# Sheet1.net
KiCad netlist of a schematic drawn in Altium Designer
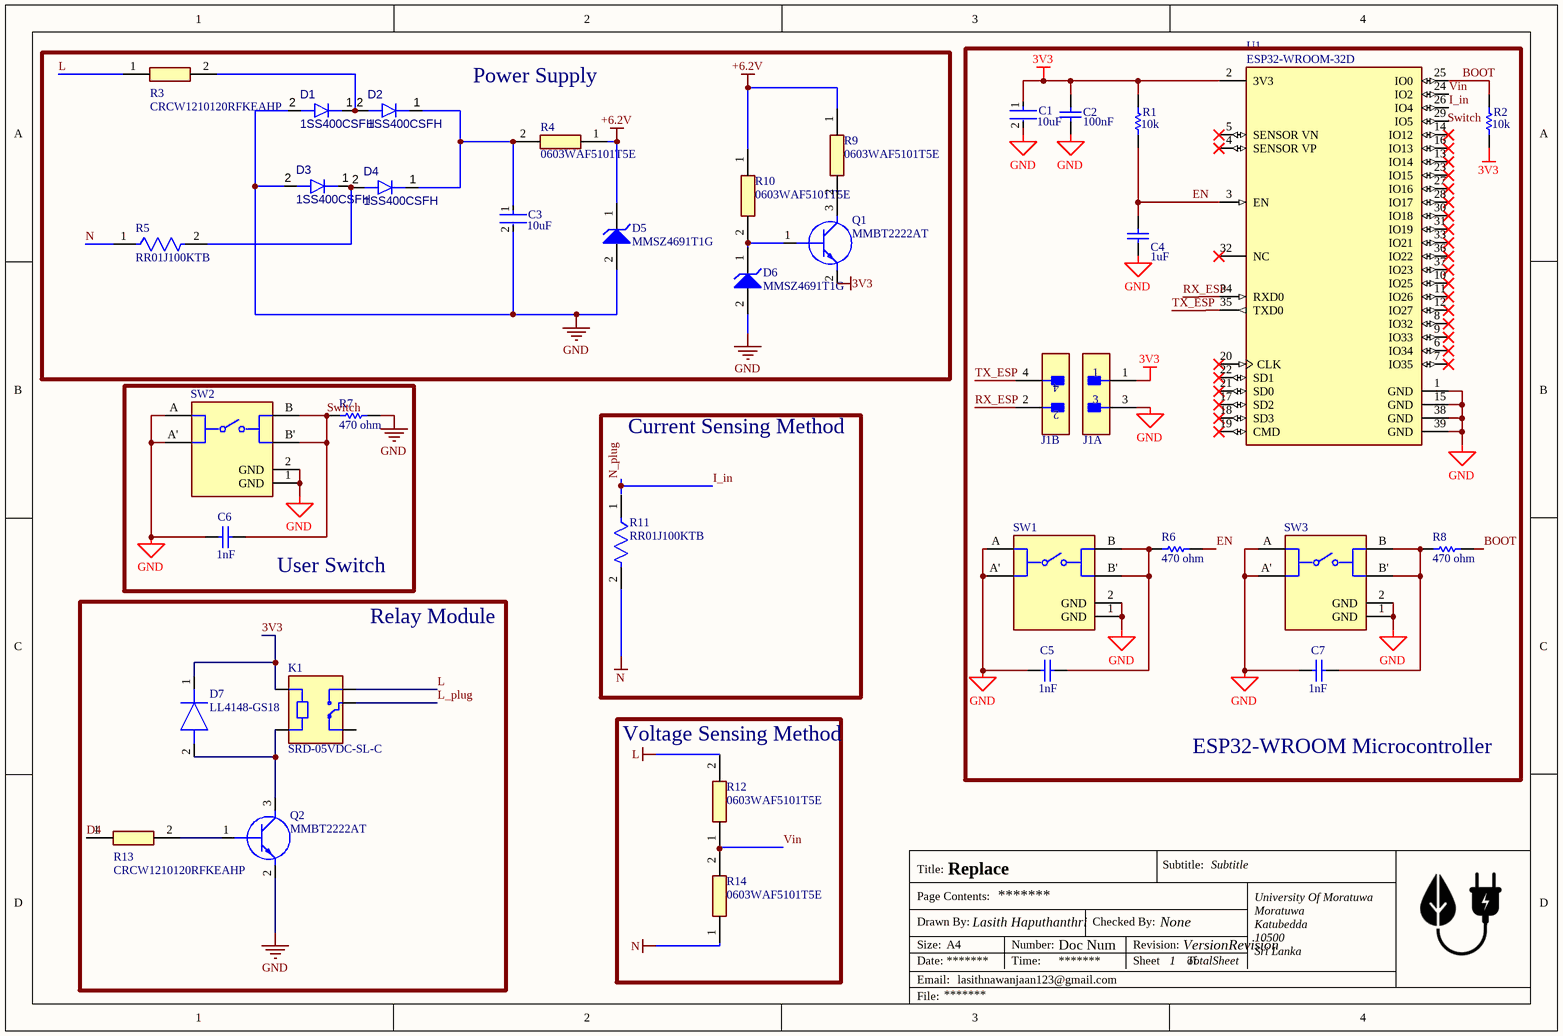
[diagram p0: Sheet1.SchDoc]

(export (version "E")
  (design (tool "Eeschema 10.0.6"))
  (components
    (comp (ref "C1")
      (value "1206YD106KAT2A")
      (footprint "FP-1206-L_3_2_0_2-W_1_6_0-IPC_B")
      (description "General Purpose Ceramic Capacitor, 1206, 10uF, 10%, X5R, 15%, 16V")
      (fields
        (field (name "TOLERANCE") "10%")
        (field (name "CAPACITANCE") "10uF")
        (field (name "VOLTAGE") "16V")
      )
      (libsource (lib "Altium Content Vault") (part "02cd4be3c70576c341d710602a673aa"))
    )
    (comp (ref "C2")
      (value "100nF")
      (footprint "CAPC2013X140X50LL20T25")
      (fields
        (field (name "MANUFACTURER") "AVX Interconnect / Elco")
        (field (name "PART NUMBER") "08055F104KAT2A")
      )
      (libsource (lib "Altium Content Vault") (part "CAP"))
    )
    (comp (ref "C3")
      (value "1206YD106KAT2A")
      (footprint "FP-1206-L_3_2_0_2-W_1_6_0-IPC_B")
      (description "General Purpose Ceramic Capacitor, 1206, 10uF, 10%, X5R, 15%, 16V")
      (fields
        (field (name "TOLERANCE") "10%")
        (field (name "CAPACITANCE") "10uF")
        (field (name "VOLTAGE") "16V")
      )
      (libsource (lib "Altium Content Vault") (part "02cd4be3c70576c341d710602a673aa"))
    )
    (comp (ref "C4")
      (value "C0805C105K4PACTU")
      (footprint "CAPC2013X145X50LL20T25")
      (fields (field (name "MANUFACTURER") "Kemet") (field (name "PARAMETER 1") "1uF"))
      (libsource (lib "Altium Content Vault") (part "CAP"))
    )
    (comp (ref "C5")
      (value "VJ0805D102KXAAJ")
      (footprint "CAPC2013X145X48LL20T23")
      (fields (field (name "MANUFACTURER") "Vitramon") (field (name "PARAMETER 1") "1nF"))
      (libsource (lib "Altium Content Vault") (part "CAP"))
    )
    (comp (ref "C6")
      (value "VJ0805D102KXAAJ")
      (footprint "CAPC2013X145X48LL20T23")
      (fields (field (name "MANUFACTURER") "Vitramon") (field (name "PARAMETER 1") "1nF"))
      (libsource (lib "Altium Content Vault") (part "CAP"))
    )
    (comp (ref "C7")
      (value "VJ0805D102KXAAJ")
      (footprint "CAPC2013X145X48LL20T23")
      (fields (field (name "MANUFACTURER") "Vitramon") (field (name "PARAMETER 1") "1nF"))
      (libsource (lib "Altium Content Vault") (part "CAP"))
    )
    (comp (ref "D1")
      (value "1SS400CSFH")
      (footprint "ROHM-VMN2-2_V")
      (description "Switching Diode (High Speed Switching), 80 V, 100 mA, 2-Pin SOD-923, RoHS, Tape and Reel")
      (libsource (lib "University of Moratuwa") (part "D-KA-2"))
    )
    (comp (ref "D2")
      (value "1SS400CSFH")
      (footprint "ROHM-VMN2-2_V")
      (description "Switching Diode (High Speed Switching), 80 V, 100 mA, 2-Pin SOD-923, RoHS, Tape and Reel")
      (libsource (lib "University of Moratuwa") (part "D-KA-2"))
    )
    (comp (ref "D3")
      (value "1SS400CSFH")
      (footprint "ROHM-VMN2-2_V")
      (description "Switching Diode (High Speed Switching), 80 V, 100 mA, 2-Pin SOD-923, RoHS, Tape and Reel")
      (libsource (lib "University of Moratuwa") (part "D-KA-2"))
    )
    (comp (ref "D4")
      (value "1SS400CSFH")
      (footprint "ROHM-VMN2-2_V")
      (description "Switching Diode (High Speed Switching), 80 V, 100 mA, 2-Pin SOD-923, RoHS, Tape and Reel")
      (libsource (lib "University of Moratuwa") (part "D-KA-2"))
    )
    (comp (ref "D5")
      (value "MMSZ4691T1G")
      (footprint "ONSC-SOD-123-2-425-04_V")
      (description "Zener Voltage Regulator, 500 mW, 2-Pin SOD-123, Pb-Free, Tape and Reel")
      (fields (field (name "MANUFACTURER") "On Semiconductor"))
      (libsource (lib "Altium Content Vault") (part "ONSC-K1A2-2"))
    )
    (comp (ref "D6")
      (value "MMSZ4691T1G")
      (footprint "ONSC-SOD-123-2-425-04_V")
      (description "Zener Voltage Regulator, 500 mW, 2-Pin SOD-123, Pb-Free, Tape and Reel")
      (fields (field (name "MANUFACTURER") "On Semiconductor"))
      (libsource (lib "Altium Content Vault") (part "ONSC-K1A2-2"))
    )
    (comp (ref "D7")
      (value "LL4148-GS18")
      (footprint "SamacSys:SOD-80")
      (description "Diode")
      (fields (field (name "MOUSER PART NUMBER") "78-LL4148-GS18"))
      (libsource (lib "*") (part "LL4148-GS18"))
    )
    (comp (ref "J1")
      (value "PEC02DABN")
      (footprint "FP-PEC02DABN-MFG")
      (description "CONN HEADER VERT 4POS 2.54MM")
      (libsource (lib "Altium Content Vault") (part "1621473add15499e993d6bbd36d0f06"))
    )
    (comp (ref "K1")
      (value "SRD-05VDC-SL-C")
      (footprint "RELAY_SRD-05VDC-SL-C")
      (fields (field (name "MF") "Songle Relay"))
      (libsource (lib "SRD-05VDC-SL-C") (part "SRD-05VDC-SL-C"))
    )
    (comp (ref "Q1")
      (value "MMBT2222AT")
      (footprint "SamacSys:SOTFL50P160X78-3N")
      (description "Transistor BJT NPN")
      (fields (field (name "MOUSER PART NUMBER") "512-MMBT2222AT"))
      (libsource (lib "*") (part "MMBT2222AT"))
    )
    (comp (ref "Q2")
      (value "MMBT2222AT")
      (footprint "SamacSys:SOTFL50P160X78-3N")
      (description "Transistor BJT NPN")
      (fields (field (name "MOUSER PART NUMBER") "512-MMBT2222AT"))
      (libsource (lib "*") (part "MMBT2222AT"))
    )
    (comp (ref "R1")
      (value "RC0805FR-0710KL")
      (footprint "RESC2013X60X35NL10T20")
      (description "Chip Resistor, 10 KOhm, +/- 1%, 0.125 W, -55 to 155 degC, 0805 (2012 Metric), RoHS, Tape and Reel")
      (fields (field (name "MANUFACTURER") "Yageo") (field (name "PARAMETER 1") "10k"))
      (libsource (lib "Altium Content Vault") (part "RES-2"))
    )
    (comp (ref "R2")
      (value "RC0805FR-0710KL")
      (footprint "RESC2013X60X35NL10T20")
      (description "Chip Resistor, 10 KOhm, +/- 1%, 0.125 W, -55 to 155 degC, 0805 (2012 Metric), RoHS, Tape and Reel")
      (fields (field (name "MANUFACTURER") "Yageo") (field (name "PARAMETER 1") "10k"))
      (libsource (lib "Altium Content Vault") (part "RES-2"))
    )
    (comp (ref "R3")
      (value "CRCW1210120RFKEAHP")
      (footprint "SamacSys:RESC3225X70N")
      (description "Resistor")
      (fields (field (name "MOUSER PART NUMBER") "71-CRCW1210120RFKEAH"))
      (libsource (lib "*") (part "CRCW1210120RFKEAHP"))
    )
    (comp (ref "R4")
      (value "0603WAF5101T5E")
      (footprint "SamacSys:RESC1608X55N")
      (description "Resistor")
      (libsource (lib "") (part "0603WAF5101T5E_2"))
    )
    (comp (ref "R5")
      (value "RR01J100KTB")
      (footprint "FP-RR01-MFG")
      (description "RES 100K OHM 5% 1W AXIAL")
      (fields (field (name "TOLERANCE") "5%"))
      (libsource (lib "Altium Content Vault") (part "1029c3af85768c4190bb7ad29bc67b5"))
    )
    (comp (ref "R6")
      (value "CRCW0805470RFKEA")
      (footprint "RESC2013X50X30LL20T20")
      (fields (field (name "MANUFACTURER") "Vishay Dale") (field (name "PARAMETER 1") "470 ohm"))
      (libsource (lib "Altium Content Vault") (part "RES"))
    )
    (comp (ref "R7")
      (value "CRCW0805470RFKEA")
      (footprint "RESC2013X50X30LL20T20")
      (fields (field (name "MANUFACTURER") "Vishay Dale") (field (name "PARAMETER 1") "470 ohm"))
      (libsource (lib "Altium Content Vault") (part "RES"))
    )
    (comp (ref "R8")
      (value "CRCW0805470RFKEA")
      (footprint "RESC2013X50X30LL20T20")
      (fields (field (name "MANUFACTURER") "Vishay Dale") (field (name "PARAMETER 1") "470 ohm"))
      (libsource (lib "Altium Content Vault") (part "RES"))
    )
    (comp (ref "R9")
      (value "0603WAF5101T5E")
      (footprint "SamacSys:RESC1608X55N")
      (description "Resistor")
      (libsource (lib "") (part "0603WAF5101T5E_1"))
    )
    (comp (ref "R10")
      (value "0603WAF5101T5E")
      (footprint "SamacSys:RESC1608X55N")
      (description "Resistor")
      (libsource (lib "") (part "0603WAF5101T5E_1"))
    )
    (comp (ref "R11")
      (value "RR01J100KTB")
      (footprint "FP-RR01-MFG")
      (description "RES 100K OHM 5% 1W AXIAL")
      (fields (field (name "TOLERANCE") "5%"))
      (libsource (lib "Altium Content Vault") (part "1029c3af85768c4190bb7ad29bc67b5"))
    )
    (comp (ref "R12")
      (value "0603WAF5101T5E")
      (footprint "SamacSys:RESC1608X55N")
      (description "Resistor")
      (libsource (lib "*") (part "0603WAF5101T5E"))
    )
    (comp (ref "R13")
      (value "CRCW1210120RFKEAHP")
      (footprint "SamacSys:RESC3225X70N")
      (description "Resistor")
      (fields (field (name "MOUSER PART NUMBER") "71-CRCW1210120RFKEAH"))
      (libsource (lib "*") (part "CRCW1210120RFKEAHP"))
    )
    (comp (ref "R14")
      (value "0603WAF5101T5E")
      (footprint "SamacSys:RESC1608X55N")
      (description "Resistor")
      (libsource (lib "*") (part "0603WAF5101T5E"))
    )
    (comp (ref "SW1")
      (value "EVQ-PLMA15")
      (footprint "FP-EVQ-PLMA15-MFG")
      (description "SWITCH TACTILE SPST-NO 0.02A 15V")
      (fields
        (field (name "OCTOPART") "https://octopart.com/evq-plma15-panasonic-39850235")
        (field (name "MANUFACTURER") "Panasonic Electronic Components")
      )
      (libsource (lib "Altium Content Vault") (part "fc7b47d2e4813f0909612a6c4f63938"))
    )
    (comp (ref "SW2")
      (value "EVQ-PLMA15")
      (footprint "FP-EVQ-PLMA15-MFG")
      (description "SWITCH TACTILE SPST-NO 0.02A 15V")
      (fields
        (field (name "OCTOPART") "https://octopart.com/evq-plma15-panasonic-39850235")
        (field (name "MANUFACTURER") "Panasonic Electronic Components")
      )
      (libsource (lib "Altium Content Vault") (part "fc7b47d2e4813f0909612a6c4f63938"))
    )
    (comp (ref "SW3")
      (value "EVQ-PLMA15")
      (footprint "FP-EVQ-PLMA15-MFG")
      (description "SWITCH TACTILE SPST-NO 0.02A 15V")
      (fields
        (field (name "OCTOPART") "https://octopart.com/evq-plma15-panasonic-39850235")
        (field (name "MANUFACTURER") "Panasonic Electronic Components")
      )
      (libsource (lib "Altium Content Vault") (part "fc7b47d2e4813f0909612a6c4f63938"))
    )
    (comp (ref "U1")
      (value "ESP32-WROOM-32D")
      (footprint "FP-ESP32-WROOM-32D-MFG")
      (description "WIFI MODULE 32MBITS SPI FLASH")
      (fields
        (field (name "OCTOPART") "https://octopart.com/esp32-wroom-32d-espressif+systems-91040050")
        (field (name "MANUFACTURER") "Espressif Systems")
      )
      (libsource (lib "Altium Content Vault") (part "a031a76f8c27026a7a7f4657ff233a3"))
    )
  )
  (nets
    (net (code "1") (name "+6.2V") (class "Default")
      (node (ref "D5") (pin "1") (pinfunction "K_1") (pintype "passive"))
      (node (ref "R10") (pin "1") (pinfunction "1_1") (pintype "passive"))
      (node (ref "R4") (pin "1") (pinfunction "1_1") (pintype "passive"))
      (node (ref "R9") (pin "1") (pinfunction "1_1") (pintype "passive"))
    )
    (net (code "2") (name "/BOOT") (class "Default")
      (node (ref "R2") (pin "2") (pinfunction "2_2") (pintype "passive"))
      (node (ref "R8") (pin "2") (pinfunction "2_2") (pintype "passive"))
      (node (ref "U1") (pin "25") (pinfunction "IO0_25") (pintype "bidirectional"))
    )
    (net (code "3") (name "/D4") (class "Default")
      (node (ref "R13") (pin "1") (pinfunction "1_1") (pintype "passive"))
    )
    (net (code "4") (name "/EN") (class "Default")
      (node (ref "C4") (pin "2") (pinfunction "2_2") (pintype "passive"))
      (node (ref "R1") (pin "1") (pinfunction "1_1") (pintype "passive"))
      (node (ref "R6") (pin "2") (pinfunction "2_2") (pintype "passive"))
      (node (ref "U1") (pin "3") (pinfunction "EN_3") (pintype "input"))
    )
    (net (code "5") (name "/I_in") (class "Default")
      (node (ref "U1") (pin "26") (pinfunction "IO4_26") (pintype "bidirectional"))
    )
    (net (code "6") (name "/L_plug") (class "Default")
      (node (ref "K1") (pin "COM") (pinfunction "COM_COM") (pintype "passive"))
    )
    (net (code "7") (name "/RX_ESP") (class "Default")
      (node (ref "J1") (pin "2") (pinfunction "2_2") (pintype "passive"))
      (node (ref "U1") (pin "34") (pinfunction "RXD0_34") (pintype "input"))
    )
    (net (code "8") (name "/Switch") (class "Default")
      (node (ref "C6") (pin "2") (pinfunction "2_2") (pintype "passive"))
      (node (ref "R7") (pin "1") (pinfunction "1_1") (pintype "passive"))
      (node (ref "SW2") (pin "B") (pinfunction "B_B") (pintype "passive"))
      (node (ref "SW2") (pin "B'") (pinfunction "B'_B'") (pintype "passive"))
    )
    (net (code "9") (name "/TX_ESP") (class "Default")
      (node (ref "J1") (pin "4") (pinfunction "4_4") (pintype "passive"))
      (node (ref "U1") (pin "35") (pinfunction "TXD0_35") (pintype "output"))
    )
    (net (code "10") (name "/Vin") (class "Default")
      (node (ref "R12") (pin "1") (pinfunction "1_1") (pintype "passive"))
      (node (ref "R14") (pin "2") (pinfunction "2_2") (pintype "passive"))
      (node (ref "U1") (pin "24") (pinfunction "IO2_24") (pintype "bidirectional"))
    )
    (net (code "11") (name "3V3") (class "Default")
      (node (ref "C1") (pin "1") (pinfunction "1_1") (pintype "passive"))
      (node (ref "C2") (pin "2") (pinfunction "2_2") (pintype "passive"))
      (node (ref "D7") (pin "1") (pinfunction "K_1") (pintype "passive"))
      (node (ref "J1") (pin "1") (pinfunction "1_1") (pintype "passive"))
      (node (ref "K1") (pin "A1") (pinfunction "A1_A1") (pintype "passive"))
      (node (ref "Q1") (pin "2") (pinfunction "E_2") (pintype "passive"))
      (node (ref "R1") (pin "2") (pinfunction "2_2") (pintype "passive"))
      (node (ref "R2") (pin "1") (pinfunction "1_1") (pintype "passive"))
      (node (ref "U1") (pin "2") (pinfunction "3V3_2") (pintype "power_in"))
    )
    (net (code "12") (name "GND") (class "Default")
      (node (ref "C1") (pin "2") (pinfunction "2_2") (pintype "passive"))
      (node (ref "C2") (pin "1") (pinfunction "1_1") (pintype "passive"))
      (node (ref "C3") (pin "2") (pinfunction "2_2") (pintype "passive"))
      (node (ref "C4") (pin "1") (pinfunction "1_1") (pintype "passive"))
      (node (ref "C5") (pin "1") (pinfunction "1_1") (pintype "passive"))
      (node (ref "C6") (pin "1") (pinfunction "1_1") (pintype "passive"))
      (node (ref "C7") (pin "1") (pinfunction "1_1") (pintype "passive"))
      (node (ref "D1") (pin "2") (pinfunction "A_2") (pintype "passive"))
      (node (ref "D3") (pin "2") (pinfunction "A_2") (pintype "passive"))
      (node (ref "D5") (pin "2") (pinfunction "A_2") (pintype "passive"))
      (node (ref "D6") (pin "2") (pinfunction "A_2") (pintype "passive"))
      (node (ref "J1") (pin "3") (pinfunction "3_3") (pintype "passive"))
      (node (ref "Q2") (pin "2") (pinfunction "E_2") (pintype "passive"))
      (node (ref "R7") (pin "2") (pinfunction "2_2") (pintype "passive"))
      (node (ref "SW1") (pin "1") (pinfunction "GND_1") (pintype "power_in"))
      (node (ref "SW1") (pin "2") (pinfunction "GND_2") (pintype "power_in"))
      (node (ref "SW1") (pin "A") (pinfunction "A_A") (pintype "passive"))
      (node (ref "SW1") (pin "A'") (pinfunction "A'_A'") (pintype "passive"))
      (node (ref "SW2") (pin "1") (pinfunction "GND_1") (pintype "power_in"))
      (node (ref "SW2") (pin "2") (pinfunction "GND_2") (pintype "power_in"))
      (node (ref "SW2") (pin "A") (pinfunction "A_A") (pintype "passive"))
      (node (ref "SW2") (pin "A'") (pinfunction "A'_A'") (pintype "passive"))
      (node (ref "SW3") (pin "1") (pinfunction "GND_1") (pintype "power_in"))
      (node (ref "SW3") (pin "2") (pinfunction "GND_2") (pintype "power_in"))
      (node (ref "SW3") (pin "A") (pinfunction "A_A") (pintype "passive"))
      (node (ref "SW3") (pin "A'") (pinfunction "A'_A'") (pintype "passive"))
      (node (ref "U1") (pin "1") (pinfunction "GND_1") (pintype "power_in"))
      (node (ref "U1") (pin "15") (pinfunction "GND_15") (pintype "power_in"))
      (node (ref "U1") (pin "38") (pinfunction "GND_38") (pintype "power_in"))
      (node (ref "U1") (pin "39") (pinfunction "GND_39") (pintype "power_in"))
    )
    (net (code "13") (name "L") (class "Default")
      (node (ref "K1") (pin "NO") (pinfunction "NO_NO") (pintype "passive"))
      (node (ref "R12") (pin "2") (pinfunction "2_2") (pintype "passive"))
      (node (ref "R3") (pin "1") (pinfunction "1_1") (pintype "passive"))
    )
    (net (code "14") (name "N") (class "Default")
      (node (ref "R11") (pin "2") (pinfunction "2_2") (pintype "passive"))
      (node (ref "R14") (pin "1") (pinfunction "1_1") (pintype "passive"))
      (node (ref "R5") (pin "1") (pinfunction "1_1") (pintype "passive"))
    )
    (net (code "15") (name "Net-(C5-Pad2)") (class "Default")
      (node (ref "C5") (pin "2") (pinfunction "2_2") (pintype "passive"))
      (node (ref "R6") (pin "1") (pinfunction "1_1") (pintype "passive"))
      (node (ref "SW1") (pin "B") (pinfunction "B_B") (pintype "passive"))
      (node (ref "SW1") (pin "B'") (pinfunction "B'_B'") (pintype "passive"))
    )
    (net (code "16") (name "Net-(C7-Pad2)") (class "Default")
      (node (ref "C7") (pin "2") (pinfunction "2_2") (pintype "passive"))
      (node (ref "R8") (pin "1") (pinfunction "1_1") (pintype "passive"))
      (node (ref "SW3") (pin "B") (pinfunction "B_B") (pintype "passive"))
      (node (ref "SW3") (pin "B'") (pinfunction "B'_B'") (pintype "passive"))
    )
    (net (code "17") (name "Net-(D1-K)") (class "Default")
      (node (ref "D1") (pin "1") (pinfunction "K_1") (pintype "passive"))
      (node (ref "D2") (pin "2") (pinfunction "A_2") (pintype "passive"))
      (node (ref "R3") (pin "2") (pinfunction "2_2") (pintype "passive"))
    )
    (net (code "18") (name "Net-(D2-K)") (class "Default")
      (node (ref "C3") (pin "1") (pinfunction "1_1") (pintype "passive"))
      (node (ref "D2") (pin "1") (pinfunction "K_1") (pintype "passive"))
      (node (ref "D4") (pin "1") (pinfunction "K_1") (pintype "passive"))
      (node (ref "R4") (pin "2") (pinfunction "2_2") (pintype "passive"))
    )
    (net (code "19") (name "Net-(D3-K)") (class "Default")
      (node (ref "D3") (pin "1") (pinfunction "K_1") (pintype "passive"))
      (node (ref "D4") (pin "2") (pinfunction "A_2") (pintype "passive"))
      (node (ref "R5") (pin "2") (pinfunction "2_2") (pintype "passive"))
    )
    (net (code "20") (name "Net-(D6-K)") (class "Default")
      (node (ref "D6") (pin "1") (pinfunction "K_1") (pintype "passive"))
      (node (ref "Q1") (pin "1") (pinfunction "B_1") (pintype "passive"))
      (node (ref "R10") (pin "2") (pinfunction "2_2") (pintype "passive"))
    )
    (net (code "21") (name "Net-(D7-A)") (class "Default")
      (node (ref "D7") (pin "2") (pinfunction "A_2") (pintype "passive"))
      (node (ref "K1") (pin "A2") (pinfunction "A2_A2") (pintype "passive"))
      (node (ref "Q2") (pin "3") (pinfunction "C_3") (pintype "passive"))
    )
    (net (code "22") (name "Net-(Q1-C)") (class "Default")
      (node (ref "Q1") (pin "3") (pinfunction "C_3") (pintype "passive"))
      (node (ref "R9") (pin "2") (pinfunction "2_2") (pintype "passive"))
    )
    (net (code "23") (name "Net-(Q2-B)") (class "Default")
      (node (ref "Q2") (pin "1") (pinfunction "B_1") (pintype "passive"))
      (node (ref "R13") (pin "2") (pinfunction "2_2") (pintype "passive"))
    )
    (net (code "24") (name "unconnected-(K1-PadNC)") (class "Default")
      (node (ref "K1") (pin "NC") (pinfunction "NC_NC") (pintype "passive"))
    )
    (net (code "25") (name "unconnected-(R11-Pad1)") (class "Default")
      (node (ref "R11") (pin "1") (pinfunction "1_1") (pintype "passive"))
    )
    (net (code "26") (name "unconnected-(U1-CLK-Pad20)") (class "Default")
      (node (ref "U1") (pin "20") (pinfunction "CLK_20") (pintype "input+no_connect"))
    )
    (net (code "27") (name "unconnected-(U1-CMD-Pad19)") (class "Default")
      (node (ref "U1") (pin "19") (pinfunction "CMD_19") (pintype "bidirectional+no_connect"))
    )
    (net (code "28") (name "unconnected-(U1-IO5-Pad29)") (class "Default")
      (node (ref "U1") (pin "29") (pinfunction "IO5_29") (pintype "bidirectional"))
    )
    (net (code "29") (name "unconnected-(U1-IO12-Pad14)") (class "Default")
      (node (ref "U1") (pin "14") (pinfunction "IO12_14") (pintype "bidirectional+no_connect"))
    )
    (net (code "30") (name "unconnected-(U1-IO13-Pad16)") (class "Default")
      (node (ref "U1") (pin "16") (pinfunction "IO13_16") (pintype "bidirectional+no_connect"))
    )
    (net (code "31") (name "unconnected-(U1-IO14-Pad13)") (class "Default")
      (node (ref "U1") (pin "13") (pinfunction "IO14_13") (pintype "bidirectional+no_connect"))
    )
    (net (code "32") (name "unconnected-(U1-IO15-Pad23)") (class "Default")
      (node (ref "U1") (pin "23") (pinfunction "IO15_23") (pintype "bidirectional+no_connect"))
    )
    (net (code "33") (name "unconnected-(U1-IO16-Pad27)") (class "Default")
      (node (ref "U1") (pin "27") (pinfunction "IO16_27") (pintype "bidirectional+no_connect"))
    )
    (net (code "34") (name "unconnected-(U1-IO17-Pad28)") (class "Default")
      (node (ref "U1") (pin "28") (pinfunction "IO17_28") (pintype "bidirectional+no_connect"))
    )
    (net (code "35") (name "unconnected-(U1-IO18-Pad30)") (class "Default")
      (node (ref "U1") (pin "30") (pinfunction "IO18_30") (pintype "bidirectional+no_connect"))
    )
    (net (code "36") (name "unconnected-(U1-IO19-Pad31)") (class "Default")
      (node (ref "U1") (pin "31") (pinfunction "IO19_31") (pintype "bidirectional+no_connect"))
    )
    (net (code "37") (name "unconnected-(U1-IO21-Pad33)") (class "Default")
      (node (ref "U1") (pin "33") (pinfunction "IO21_33") (pintype "bidirectional+no_connect"))
    )
    (net (code "38") (name "unconnected-(U1-IO22-Pad36)") (class "Default")
      (node (ref "U1") (pin "36") (pinfunction "IO22_36") (pintype "bidirectional+no_connect"))
    )
    (net (code "39") (name "unconnected-(U1-IO23-Pad37)") (class "Default")
      (node (ref "U1") (pin "37") (pinfunction "IO23_37") (pintype "bidirectional+no_connect"))
    )
    (net (code "40") (name "unconnected-(U1-IO25-Pad10)") (class "Default")
      (node (ref "U1") (pin "10") (pinfunction "IO25_10") (pintype "bidirectional+no_connect"))
    )
    (net (code "41") (name "unconnected-(U1-IO26-Pad11)") (class "Default")
      (node (ref "U1") (pin "11") (pinfunction "IO26_11") (pintype "bidirectional+no_connect"))
    )
    (net (code "42") (name "unconnected-(U1-IO27-Pad12)") (class "Default")
      (node (ref "U1") (pin "12") (pinfunction "IO27_12") (pintype "bidirectional+no_connect"))
    )
    (net (code "43") (name "unconnected-(U1-IO32-Pad8)") (class "Default")
      (node (ref "U1") (pin "8") (pinfunction "IO32_8") (pintype "bidirectional+no_connect"))
    )
    (net (code "44") (name "unconnected-(U1-IO33-Pad9)") (class "Default")
      (node (ref "U1") (pin "9") (pinfunction "IO33_9") (pintype "bidirectional+no_connect"))
    )
    (net (code "45") (name "unconnected-(U1-IO34-Pad6)") (class "Default")
      (node (ref "U1") (pin "6") (pinfunction "IO34_6") (pintype "bidirectional+no_connect"))
    )
    (net (code "46") (name "unconnected-(U1-IO35-Pad7)") (class "Default")
      (node (ref "U1") (pin "7") (pinfunction "IO35_7") (pintype "bidirectional+no_connect"))
    )
    (net (code "47") (name "unconnected-(U1-NC-Pad32)") (class "Default")
      (node (ref "U1") (pin "32") (pinfunction "NC_32") (pintype "passive+no_connect"))
    )
    (net (code "48") (name "unconnected-(U1-SD0-Pad21)") (class "Default")
      (node (ref "U1") (pin "21") (pinfunction "SD0_21") (pintype "bidirectional+no_connect"))
    )
    (net (code "49") (name "unconnected-(U1-SD1-Pad22)") (class "Default")
      (node (ref "U1") (pin "22") (pinfunction "SD1_22") (pintype "bidirectional+no_connect"))
    )
    (net (code "50") (name "unconnected-(U1-SD2-Pad17)") (class "Default")
      (node (ref "U1") (pin "17") (pinfunction "SD2_17") (pintype "bidirectional+no_connect"))
    )
    (net (code "51") (name "unconnected-(U1-SD3-Pad18)") (class "Default")
      (node (ref "U1") (pin "18") (pinfunction "SD3_18") (pintype "bidirectional+no_connect"))
    )
    (net (code "52") (name "unconnected-(U1-SENSOR_VN-Pad5)") (class "Default")
      (node (ref "U1") (pin "5") (pinfunction "SENSOR_VN_5") (pintype "bidirectional+no_connect"))
    )
    (net (code "53") (name "unconnected-(U1-SENSOR_VP-Pad4)") (class "Default")
      (node (ref "U1") (pin "4") (pinfunction "SENSOR_VP_4") (pintype "bidirectional+no_connect"))
    )
  )
)
